# jlink-ob.net
KiCad netlist of a schematic drawn in Altium Designer
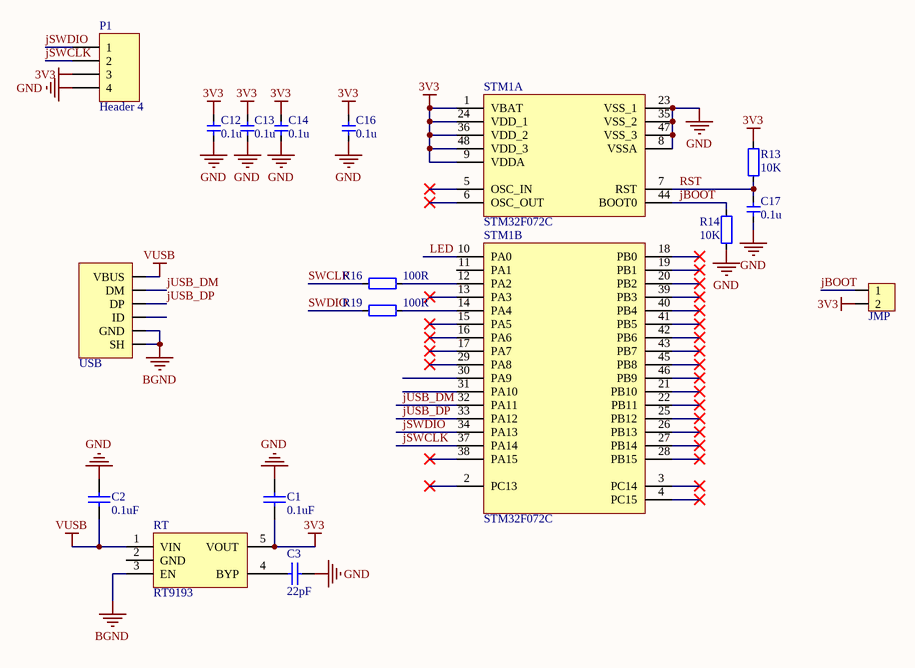
[diagram p0: jlink-ob.SchDoc]

(export (version "E")
  (design (tool "Eeschema 10.0.6"))
  (components
    (comp (ref "C1")
      (value "0.1uF")
      (footprint "0805C")
      (description "Capacitor")
      (fields (field (name "Comment") "Cap") (field (name "PUBLISHER") "Altium Limited"))
      (libsource (lib "K60-mainboard-v3.1") (part "Cap"))
    )
    (comp (ref "C2")
      (value "0.1uF")
      (footprint "0805C")
      (description "Capacitor")
      (fields (field (name "Comment") "Cap") (field (name "PUBLISHER") "Altium Limited"))
      (libsource (lib "K60-mainboard-v3.1") (part "Cap"))
    )
    (comp (ref "C3")
      (value "22pF")
      (footprint "0805C")
      (description "Capacitor")
      (fields (field (name "Comment") "Cap") (field (name "PUBLISHER") "Altium Limited"))
      (libsource (lib "K60-mainboard-v3.1") (part "Cap"))
    )
    (comp (ref "C12")
      (value "0.1u")
      (footprint "PCB_PassiveCap:CAP_0603")
      (description "Capacitor")
      (fields (field (name "Comment") "Cap_0603"))
      (libsource (lib "SCH_Passive") (part "Cap_0603"))
    )
    (comp (ref "C13")
      (value "0.1u")
      (footprint "PCB_PassiveCap:CAP_0603")
      (description "Capacitor")
      (fields (field (name "Comment") "Cap_0603"))
      (libsource (lib "SCH_Passive") (part "Cap_0603"))
    )
    (comp (ref "C14")
      (value "0.1u")
      (footprint "PCB_PassiveCap:CAP_0603")
      (description "Capacitor")
      (fields (field (name "Comment") "Cap_0603"))
      (libsource (lib "SCH_Passive") (part "Cap_0603"))
    )
    (comp (ref "C16")
      (value "0.1u")
      (footprint "PCB_PassiveCap:CAP_0603")
      (description "Capacitor")
      (fields (field (name "Comment") "Cap_0603"))
      (libsource (lib "SCH_Passive") (part "Cap_0603"))
    )
    (comp (ref "C17")
      (value "0.1u")
      (footprint "PCB_PassiveCap:CAP_0603")
      (description "Capacitor")
      (fields (field (name "Comment") "Cap_0603"))
      (libsource (lib "SCH_Passive") (part "Cap_0603"))
    )
    (comp (ref "JMP")
      (value "HDR1x2_2.54")
      (footprint "PCB_ConnectorHDR:HDR1X2_2.54_180")
      (description "Header")
      (libsource (lib "SCH_ConnectorHDR") (part "HDR1x2_2.54"))
    )
    (comp (ref "P1")
      (value "Header 4")
      (footprint "HDR1X4")
      (description "Header, 4-Pin")
      (fields (field (name "PUBLISHER") "Altium Limited"))
      (libsource (lib "K60-mainboard-v3.1") (part "Header 4"))
    )
    (comp (ref "R13")
      (value "10K")
      (footprint "PCB_PassiveRes:RES_0603")
      (description "Resistor")
      (fields (field (name "Comment") "Res_0603"))
      (libsource (lib "") (part "Res_0603_1"))
    )
    (comp (ref "R14")
      (value "10K")
      (footprint "PCB_PassiveRes:RES_0603")
      (description "Resistor")
      (fields (field (name "Comment") "Res_0603"))
      (libsource (lib "") (part "Res_0603_1"))
    )
    (comp (ref "R16")
      (value "100R")
      (footprint "PCB_PassiveRes:RES_0603")
      (description "Resistor")
      (fields (field (name "Comment") "Res_0603"))
      (libsource (lib "SCH_Passive") (part "Res_0603"))
    )
    (comp (ref "R19")
      (value "100R")
      (footprint "PCB_PassiveRes:RES_0603")
      (description "Resistor")
      (fields (field (name "Comment") "Res_0603"))
      (libsource (lib "SCH_Passive") (part "Res_0603"))
    )
    (comp (ref "RT")
      (value "RT9193")
      (footprint "PCB_IntegratedCircuit:SOT23-5")
      (description "Power")
      (libsource (lib "SCH_IntegratedCircuit") (part "RT9193"))
    )
    (comp (ref "STM1")
      (value "STM32F072C")
      (footprint "PCB_IntegratedCircuit:LQFP_P0.5_48")
      (description "MCU")
      (libsource (lib "SCH_IntegratedCircuit") (part "STM32F103C"))
    )
    (comp (ref "USB")
      (value "USB_Micro")
      (footprint "PCB_USB:USB_Micro-AB")
      (description "USB")
      (libsource (lib "SCH_USB") (part "USB_Micro"))
    )
  )
  (nets
    (net (code "1") (name "/LED") (class "Default")
      (node (ref "STM1") (pin "10") (pinfunction "PA0_10") (pintype "passive"))
    )
    (net (code "2") (name "/RST") (class "Default")
      (node (ref "C17") (pin "2") (pinfunction "2_2") (pintype "passive"))
      (node (ref "R13") (pin "1") (pinfunction "1_1") (pintype "passive"))
      (node (ref "STM1") (pin "7") (pinfunction "RST_7") (pintype "passive"))
    )
    (net (code "3") (name "/SWCLK") (class "Default")
      (node (ref "R16") (pin "1") (pinfunction "1_1") (pintype "passive"))
    )
    (net (code "4") (name "/SWDIO") (class "Default")
      (node (ref "R19") (pin "1") (pinfunction "1_1") (pintype "passive"))
    )
    (net (code "5") (name "/jBOOT") (class "Default")
      (node (ref "JMP") (pin "1") (pinfunction "1_1") (pintype "passive"))
      (node (ref "R14") (pin "2") (pinfunction "2_2") (pintype "passive"))
      (node (ref "STM1") (pin "44") (pinfunction "BOOT0_44") (pintype "passive"))
    )
    (net (code "6") (name "/jSWCLK") (class "Default")
      (node (ref "P1") (pin "2") (pinfunction "2_2") (pintype "passive"))
      (node (ref "STM1") (pin "37") (pinfunction "PA14_37") (pintype "passive"))
    )
    (net (code "7") (name "/jSWDIO") (class "Default")
      (node (ref "P1") (pin "1") (pinfunction "1_1") (pintype "passive"))
      (node (ref "STM1") (pin "34") (pinfunction "PA13_34") (pintype "passive"))
    )
    (net (code "8") (name "/jUSB_DM") (class "Default")
      (node (ref "STM1") (pin "32") (pinfunction "PA11_32") (pintype "passive"))
      (node (ref "USB") (pin "2") (pinfunction "DM_2") (pintype "passive"))
    )
    (net (code "9") (name "/jUSB_DP") (class "Default")
      (node (ref "STM1") (pin "33") (pinfunction "PA12_33") (pintype "passive"))
      (node (ref "USB") (pin "3") (pinfunction "DP_3") (pintype "passive"))
    )
    (net (code "10") (name "3V3") (class "Default")
      (node (ref "C1") (pin "1") (pinfunction "1_1") (pintype "passive"))
      (node (ref "C12") (pin "1") (pinfunction "1_1") (pintype "passive"))
      (node (ref "C13") (pin "1") (pinfunction "1_1") (pintype "passive"))
      (node (ref "C14") (pin "1") (pinfunction "1_1") (pintype "passive"))
      (node (ref "C16") (pin "2") (pinfunction "2_2") (pintype "passive"))
      (node (ref "JMP") (pin "2") (pinfunction "2_2") (pintype "passive"))
      (node (ref "P1") (pin "3") (pinfunction "3_3") (pintype "passive"))
      (node (ref "R13") (pin "2") (pinfunction "2_2") (pintype "passive"))
      (node (ref "RT") (pin "5") (pinfunction "VOUT_5") (pintype "passive"))
      (node (ref "STM1") (pin "1") (pinfunction "VBAT_1") (pintype "passive"))
      (node (ref "STM1") (pin "24") (pinfunction "VDD_1_24") (pintype "passive"))
      (node (ref "STM1") (pin "36") (pinfunction "VDD_2_36") (pintype "passive"))
      (node (ref "STM1") (pin "48") (pinfunction "VDD_3_48") (pintype "passive"))
      (node (ref "STM1") (pin "9") (pinfunction "VDDA_9") (pintype "passive"))
    )
    (net (code "11") (name "BGND") (class "Default")
      (node (ref "RT") (pin "3") (pinfunction "EN_3") (pintype "power_in"))
      (node (ref "USB") (pin "0") (pinfunction "SH_0") (pintype "passive"))
      (node (ref "USB") (pin "5") (pinfunction "GND_5") (pintype "passive"))
    )
    (net (code "12") (name "GND") (class "Default")
      (node (ref "C1") (pin "2") (pinfunction "2_2") (pintype "passive"))
      (node (ref "C12") (pin "2") (pinfunction "2_2") (pintype "passive"))
      (node (ref "C13") (pin "2") (pinfunction "2_2") (pintype "passive"))
      (node (ref "C14") (pin "2") (pinfunction "2_2") (pintype "passive"))
      (node (ref "C16") (pin "1") (pinfunction "1_1") (pintype "passive"))
      (node (ref "C17") (pin "1") (pinfunction "1_1") (pintype "passive"))
      (node (ref "C2") (pin "2") (pinfunction "2_2") (pintype "passive"))
      (node (ref "C3") (pin "2") (pinfunction "2_2") (pintype "passive"))
      (node (ref "P1") (pin "4") (pinfunction "4_4") (pintype "passive"))
      (node (ref "R14") (pin "1") (pinfunction "1_1") (pintype "passive"))
      (node (ref "STM1") (pin "23") (pinfunction "VSS_1_23") (pintype "passive"))
      (node (ref "STM1") (pin "35") (pinfunction "VSS_2_35") (pintype "passive"))
      (node (ref "STM1") (pin "47") (pinfunction "VSS_3_47") (pintype "passive"))
      (node (ref "STM1") (pin "8") (pinfunction "VSSA_8") (pintype "passive"))
    )
    (net (code "13") (name "Net-(RT-BYP)") (class "Default")
      (node (ref "C3") (pin "1") (pinfunction "1_1") (pintype "passive"))
      (node (ref "RT") (pin "4") (pinfunction "BYP_4") (pintype "passive"))
    )
    (net (code "14") (name "Net-(STM1B-PA2)") (class "Default")
      (node (ref "R16") (pin "2") (pinfunction "2_2") (pintype "passive"))
      (node (ref "STM1") (pin "12") (pinfunction "PA2_12") (pintype "passive"))
    )
    (net (code "15") (name "Net-(STM1B-PA4)") (class "Default")
      (node (ref "R19") (pin "2") (pinfunction "2_2") (pintype "passive"))
      (node (ref "STM1") (pin "14") (pinfunction "PA4_14") (pintype "passive"))
    )
    (net (code "16") (name "VUSB") (class "Default")
      (node (ref "C2") (pin "1") (pinfunction "1_1") (pintype "passive"))
      (node (ref "RT") (pin "1") (pinfunction "VIN_1") (pintype "passive"))
      (node (ref "USB") (pin "1") (pinfunction "VBUS_1") (pintype "passive"))
    )
    (net (code "17") (name "unconnected-(RT-GND-Pad2)") (class "Default")
      (node (ref "RT") (pin "2") (pinfunction "GND_2") (pintype "passive"))
    )
    (net (code "18") (name "unconnected-(STM1A-OSC_IN-Pad5)") (class "Default")
      (node (ref "STM1") (pin "5") (pinfunction "OSC_IN_5") (pintype "passive+no_connect"))
    )
    (net (code "19") (name "unconnected-(STM1A-OSC_OUT-Pad6)") (class "Default")
      (node (ref "STM1") (pin "6") (pinfunction "OSC_OUT_6") (pintype "passive+no_connect"))
    )
    (net (code "20") (name "unconnected-(STM1B-PA1-Pad11)") (class "Default")
      (node (ref "STM1") (pin "11") (pinfunction "PA1_11") (pintype "passive"))
    )
    (net (code "21") (name "unconnected-(STM1B-PA3-Pad13)") (class "Default")
      (node (ref "STM1") (pin "13") (pinfunction "PA3_13") (pintype "passive+no_connect"))
    )
    (net (code "22") (name "unconnected-(STM1B-PA5-Pad15)") (class "Default")
      (node (ref "STM1") (pin "15") (pinfunction "PA5_15") (pintype "passive+no_connect"))
    )
    (net (code "23") (name "unconnected-(STM1B-PA6-Pad16)") (class "Default")
      (node (ref "STM1") (pin "16") (pinfunction "PA6_16") (pintype "passive+no_connect"))
    )
    (net (code "24") (name "unconnected-(STM1B-PA7-Pad17)") (class "Default")
      (node (ref "STM1") (pin "17") (pinfunction "PA7_17") (pintype "passive+no_connect"))
    )
    (net (code "25") (name "unconnected-(STM1B-PA8-Pad29)") (class "Default")
      (node (ref "STM1") (pin "29") (pinfunction "PA8_29") (pintype "passive+no_connect"))
    )
    (net (code "26") (name "unconnected-(STM1B-PA9-Pad30)") (class "Default")
      (node (ref "STM1") (pin "30") (pinfunction "PA9_30") (pintype "passive"))
    )
    (net (code "27") (name "unconnected-(STM1B-PA10-Pad31)") (class "Default")
      (node (ref "STM1") (pin "31") (pinfunction "PA10_31") (pintype "passive"))
    )
    (net (code "28") (name "unconnected-(STM1B-PA15-Pad38)") (class "Default")
      (node (ref "STM1") (pin "38") (pinfunction "PA15_38") (pintype "passive+no_connect"))
    )
    (net (code "29") (name "unconnected-(STM1B-PB0-Pad18)") (class "Default")
      (node (ref "STM1") (pin "18") (pinfunction "PB0_18") (pintype "passive+no_connect"))
    )
    (net (code "30") (name "unconnected-(STM1B-PB1-Pad19)") (class "Default")
      (node (ref "STM1") (pin "19") (pinfunction "PB1_19") (pintype "passive+no_connect"))
    )
    (net (code "31") (name "unconnected-(STM1B-PB2-Pad20)") (class "Default")
      (node (ref "STM1") (pin "20") (pinfunction "PB2_20") (pintype "passive+no_connect"))
    )
    (net (code "32") (name "unconnected-(STM1B-PB3-Pad39)") (class "Default")
      (node (ref "STM1") (pin "39") (pinfunction "PB3_39") (pintype "passive+no_connect"))
    )
    (net (code "33") (name "unconnected-(STM1B-PB4-Pad40)") (class "Default")
      (node (ref "STM1") (pin "40") (pinfunction "PB4_40") (pintype "passive+no_connect"))
    )
    (net (code "34") (name "unconnected-(STM1B-PB5-Pad41)") (class "Default")
      (node (ref "STM1") (pin "41") (pinfunction "PB5_41") (pintype "passive+no_connect"))
    )
    (net (code "35") (name "unconnected-(STM1B-PB6-Pad42)") (class "Default")
      (node (ref "STM1") (pin "42") (pinfunction "PB6_42") (pintype "passive+no_connect"))
    )
    (net (code "36") (name "unconnected-(STM1B-PB7-Pad43)") (class "Default")
      (node (ref "STM1") (pin "43") (pinfunction "PB7_43") (pintype "passive+no_connect"))
    )
    (net (code "37") (name "unconnected-(STM1B-PB8-Pad45)") (class "Default")
      (node (ref "STM1") (pin "45") (pinfunction "PB8_45") (pintype "passive+no_connect"))
    )
    (net (code "38") (name "unconnected-(STM1B-PB9-Pad46)") (class "Default")
      (node (ref "STM1") (pin "46") (pinfunction "PB9_46") (pintype "passive+no_connect"))
    )
    (net (code "39") (name "unconnected-(STM1B-PB10-Pad21)") (class "Default")
      (node (ref "STM1") (pin "21") (pinfunction "PB10_21") (pintype "passive+no_connect"))
    )
    (net (code "40") (name "unconnected-(STM1B-PB11-Pad22)") (class "Default")
      (node (ref "STM1") (pin "22") (pinfunction "PB11_22") (pintype "passive+no_connect"))
    )
    (net (code "41") (name "unconnected-(STM1B-PB12-Pad25)") (class "Default")
      (node (ref "STM1") (pin "25") (pinfunction "PB12_25") (pintype "passive+no_connect"))
    )
    (net (code "42") (name "unconnected-(STM1B-PB13-Pad26)") (class "Default")
      (node (ref "STM1") (pin "26") (pinfunction "PB13_26") (pintype "passive+no_connect"))
    )
    (net (code "43") (name "unconnected-(STM1B-PB14-Pad27)") (class "Default")
      (node (ref "STM1") (pin "27") (pinfunction "PB14_27") (pintype "passive+no_connect"))
    )
    (net (code "44") (name "unconnected-(STM1B-PB15-Pad28)") (class "Default")
      (node (ref "STM1") (pin "28") (pinfunction "PB15_28") (pintype "passive+no_connect"))
    )
    (net (code "45") (name "unconnected-(STM1B-PC13-Pad2)") (class "Default")
      (node (ref "STM1") (pin "2") (pinfunction "PC13_2") (pintype "passive+no_connect"))
    )
    (net (code "46") (name "unconnected-(STM1B-PC14-Pad3)") (class "Default")
      (node (ref "STM1") (pin "3") (pinfunction "PC14_3") (pintype "passive+no_connect"))
    )
    (net (code "47") (name "unconnected-(STM1B-PC15-Pad4)") (class "Default")
      (node (ref "STM1") (pin "4") (pinfunction "PC15_4") (pintype "passive+no_connect"))
    )
    (net (code "48") (name "unconnected-(USB-ID-Pad4)") (class "Default")
      (node (ref "USB") (pin "4") (pinfunction "ID_4") (pintype "passive"))
    )
  )
)
